# SD_Card_WCN_RF.net
KiCad netlist of a schematic drawn in Altium Designer
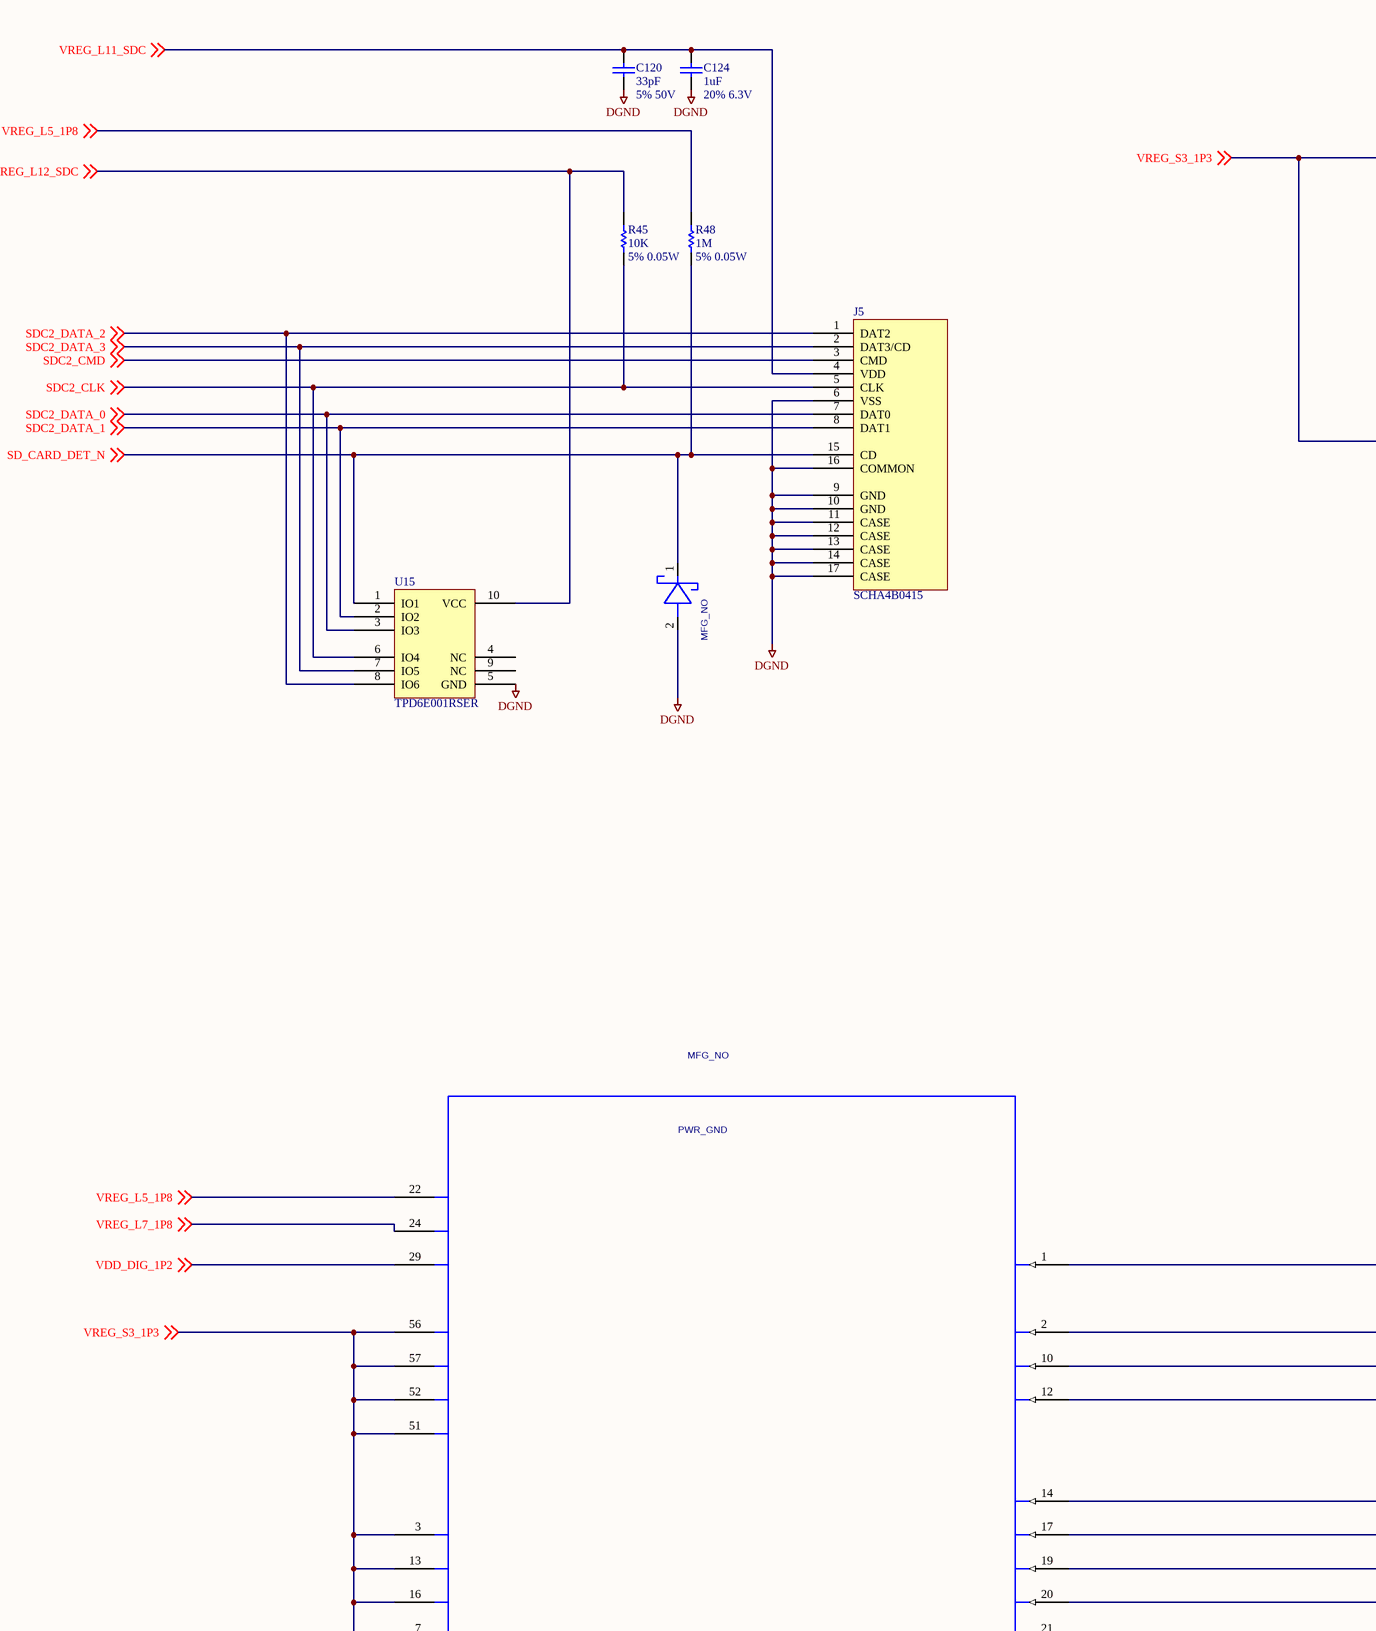
[diagram p0: SD Card_WCN_RF.SchDoc, top left]
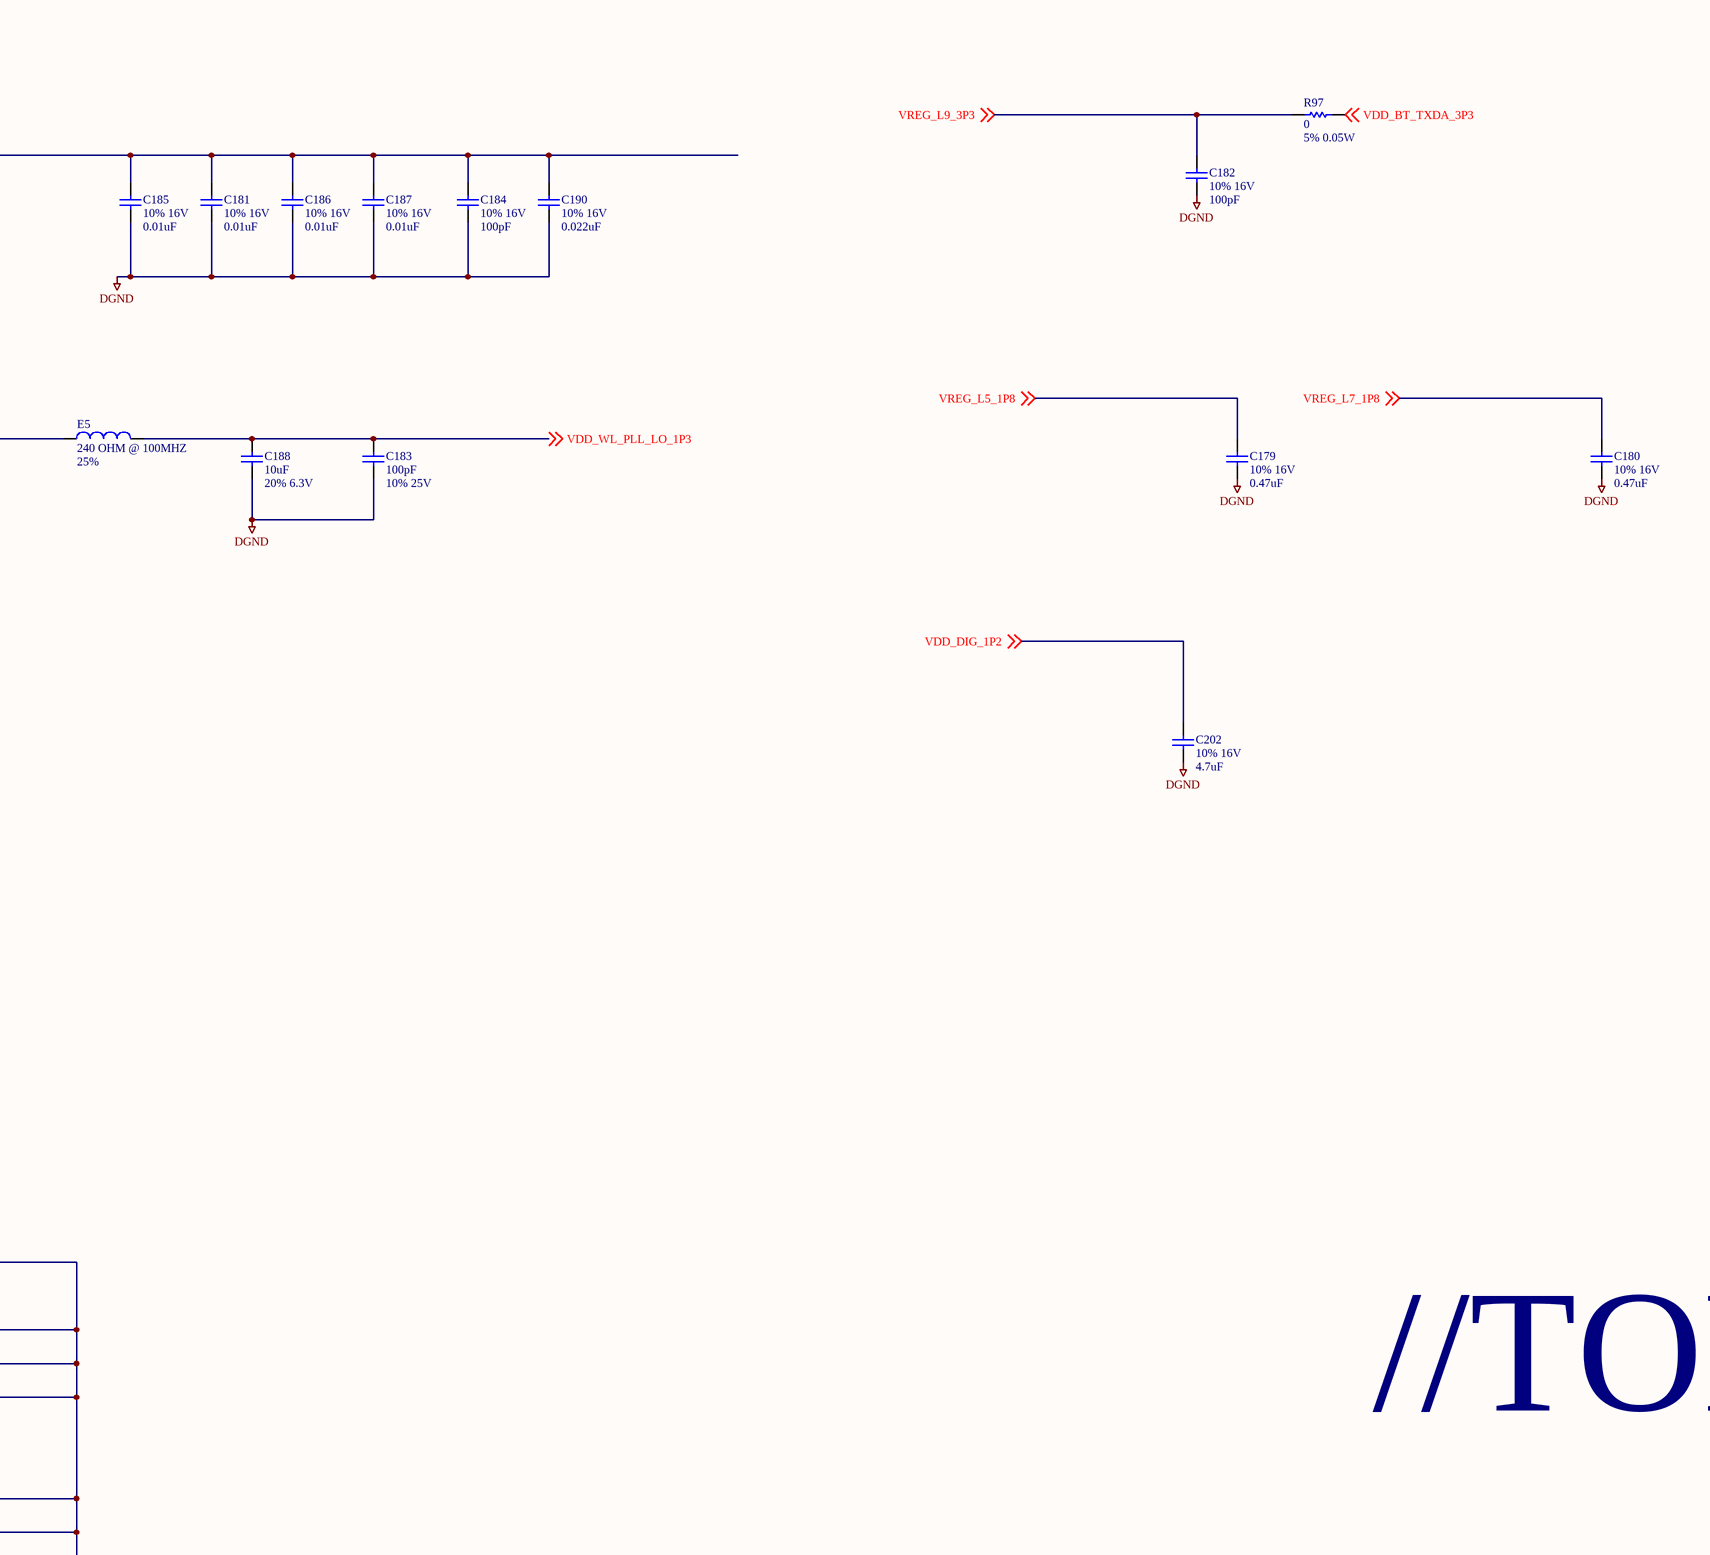
[diagram p1: SD Card_WCN_RF.SchDoc, top middle]
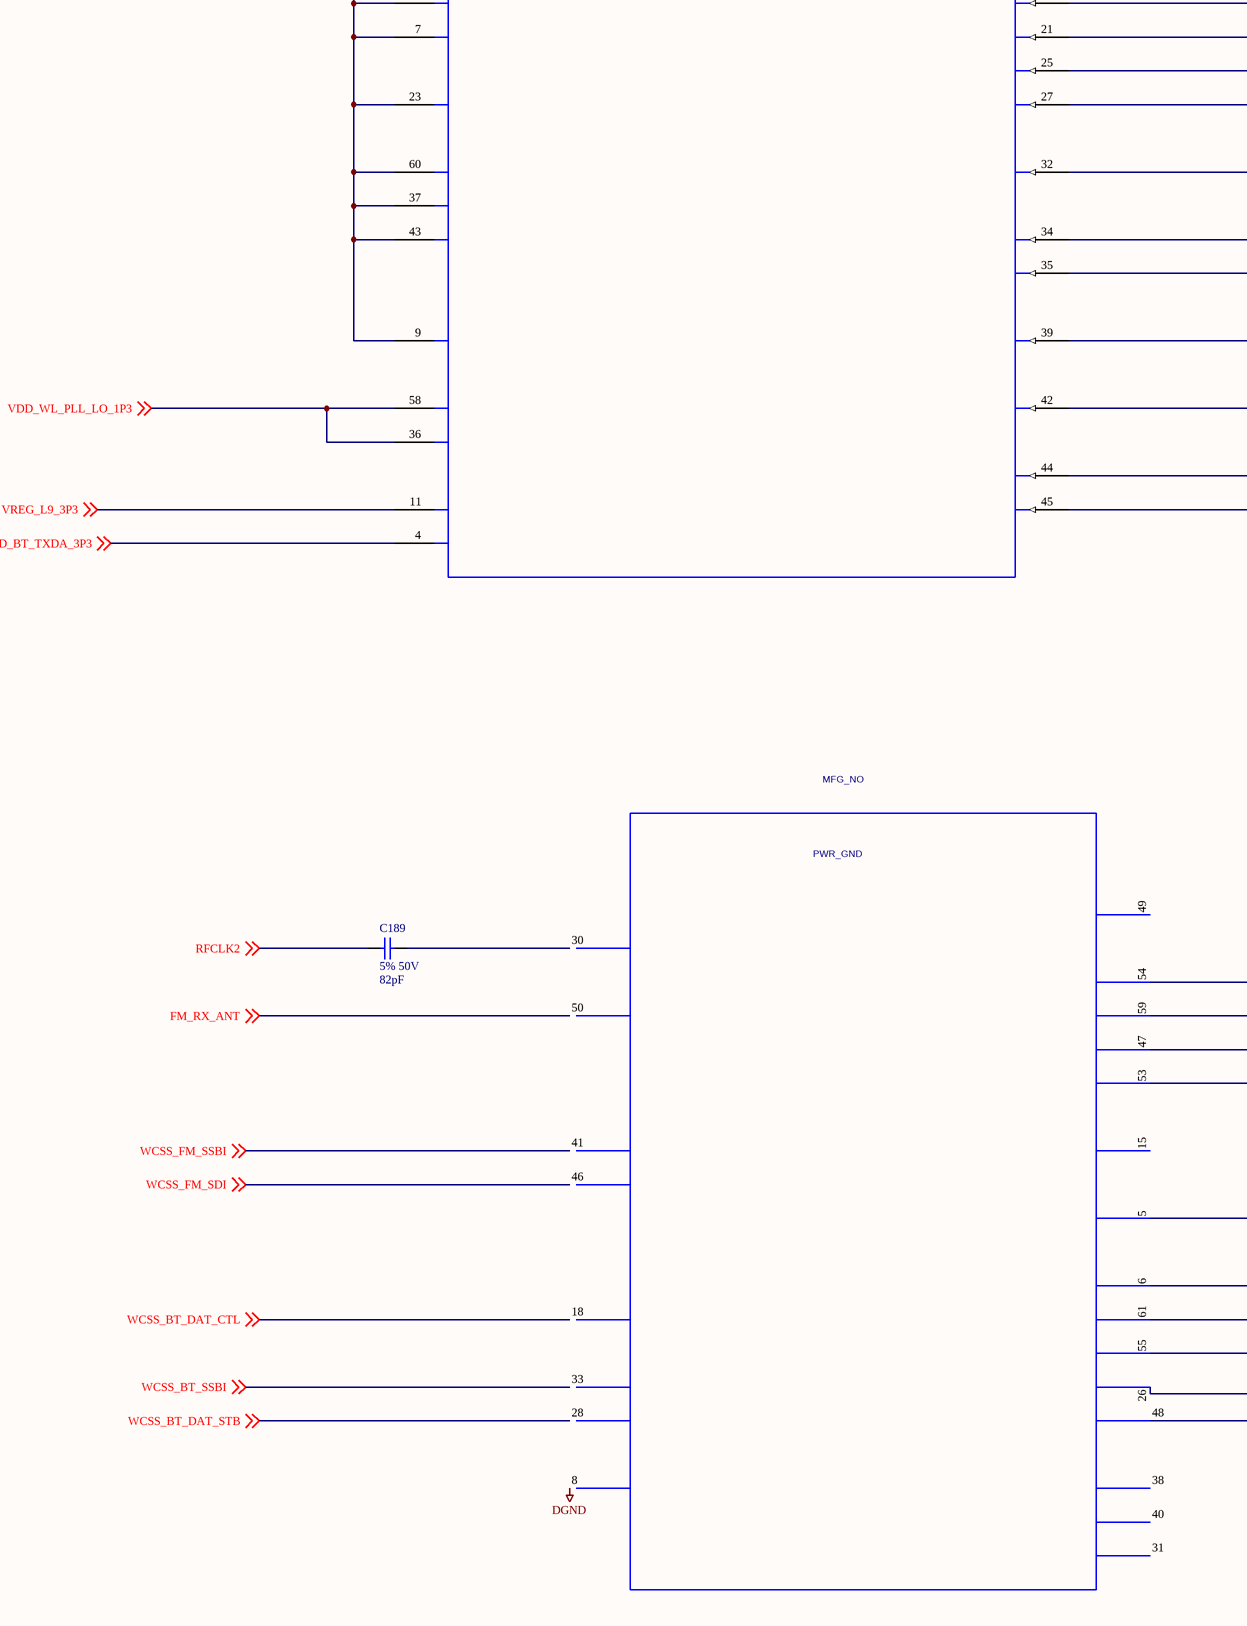
[diagram p2: SD Card_WCN_RF.SchDoc, bottom left]
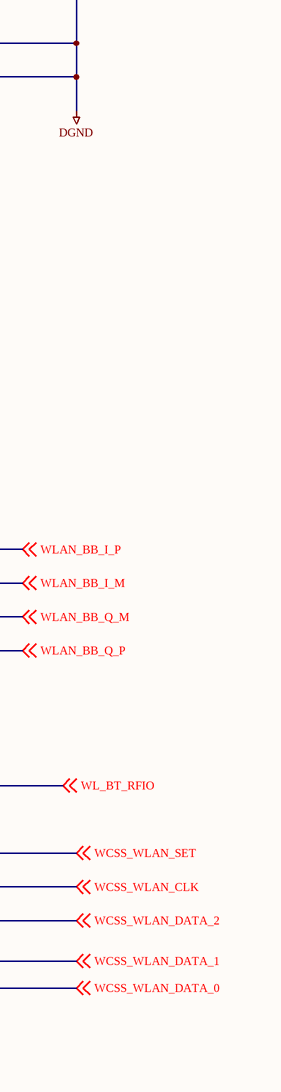
[diagram p3: SD Card_WCN_RF.SchDoc, bottom middle]

(export (version "E")
  (design (tool "Eeschema 10.0.6"))
  (components
    (comp (ref "C120")
      (value "33pF")
      (footprint "RAD-0.3")
      (description "Capacitor")
      (fields (field (name "ALTIUM_VALUE") "5% 50V") (field (name "PUBLISHER") "Altium Limited"))
      (libsource (lib "Miscellaneous Devices") (part "Cap"))
    )
    (comp (ref "C124")
      (value "1uF")
      (footprint "RAD-0.3")
      (description "Capacitor")
      (fields (field (name "ALTIUM_VALUE") "20% 6.3V") (field (name "PUBLISHER") "Altium Limited"))
      (libsource (lib "Miscellaneous Devices") (part "Cap"))
    )
    (comp (ref "C179")
      (value "10% 16V")
      (footprint "RAD-0.3")
      (description "Capacitor")
      (fields (field (name "ALTIUM_VALUE") "0.47uF") (field (name "PUBLISHER") "Altium Limited"))
      (libsource (lib "Miscellaneous Devices") (part "Cap"))
    )
    (comp (ref "C180")
      (value "10% 16V")
      (footprint "RAD-0.3")
      (description "Capacitor")
      (fields (field (name "ALTIUM_VALUE") "0.47uF") (field (name "PUBLISHER") "Altium Limited"))
      (libsource (lib "Miscellaneous Devices") (part "Cap"))
    )
    (comp (ref "C181")
      (value "10% 16V")
      (footprint "RAD-0.3")
      (description "Capacitor")
      (fields (field (name "ALTIUM_VALUE") "0.01uF") (field (name "PUBLISHER") "Altium Limited"))
      (libsource (lib "Miscellaneous Devices") (part "Cap"))
    )
    (comp (ref "C182")
      (value "10% 16V")
      (footprint "RAD-0.3")
      (description "Capacitor")
      (fields (field (name "ALTIUM_VALUE") "100pF") (field (name "PUBLISHER") "Altium Limited"))
      (libsource (lib "Miscellaneous Devices") (part "Cap"))
    )
    (comp (ref "C183")
      (value "100pF")
      (footprint "RAD-0.3")
      (description "Capacitor")
      (fields (field (name "ALTIUM_VALUE") "10% 25V") (field (name "PUBLISHER") "Altium Limited"))
      (libsource (lib "Miscellaneous Devices") (part "Cap"))
    )
    (comp (ref "C184")
      (value "10% 16V")
      (footprint "RAD-0.3")
      (description "Capacitor")
      (fields (field (name "ALTIUM_VALUE") "100pF") (field (name "PUBLISHER") "Altium Limited"))
      (libsource (lib "Miscellaneous Devices") (part "Cap"))
    )
    (comp (ref "C185")
      (value "10% 16V")
      (footprint "RAD-0.3")
      (description "Capacitor")
      (fields (field (name "ALTIUM_VALUE") "0.01uF") (field (name "PUBLISHER") "Altium Limited"))
      (libsource (lib "Miscellaneous Devices") (part "Cap"))
    )
    (comp (ref "C186")
      (value "10% 16V")
      (footprint "RAD-0.3")
      (description "Capacitor")
      (fields (field (name "ALTIUM_VALUE") "0.01uF") (field (name "PUBLISHER") "Altium Limited"))
      (libsource (lib "Miscellaneous Devices") (part "Cap"))
    )
    (comp (ref "C187")
      (value "10% 16V")
      (footprint "RAD-0.3")
      (description "Capacitor")
      (fields (field (name "ALTIUM_VALUE") "0.01uF") (field (name "PUBLISHER") "Altium Limited"))
      (libsource (lib "Miscellaneous Devices") (part "Cap"))
    )
    (comp (ref "C188")
      (value "10uF")
      (footprint "RAD-0.3")
      (description "Capacitor")
      (fields (field (name "ALTIUM_VALUE") "20% 6.3V") (field (name "PUBLISHER") "Altium Limited"))
      (libsource (lib "Miscellaneous Devices") (part "Cap"))
    )
    (comp (ref "C189")
      (value "5% 50V")
      (footprint "RAD-0.3")
      (description "Capacitor")
      (fields (field (name "ALTIUM_VALUE") "82pF") (field (name "PUBLISHER") "Altium Limited"))
      (libsource (lib "Miscellaneous Devices") (part "Cap"))
    )
    (comp (ref "C190")
      (value "10% 16V")
      (footprint "RAD-0.3")
      (description "Capacitor")
      (fields (field (name "ALTIUM_VALUE") "0.022uF") (field (name "PUBLISHER") "Altium Limited"))
      (libsource (lib "Miscellaneous Devices") (part "Cap"))
    )
    (comp (ref "C202")
      (value "10% 16V")
      (footprint "RAD-0.3")
      (description "Capacitor")
      (fields (field (name "ALTIUM_VALUE") "4.7uF") (field (name "PUBLISHER") "Altium Limited"))
      (libsource (lib "Miscellaneous Devices") (part "Cap"))
    )
    (comp (ref "CR24")
      (value "ESD7C5")
      (fields (field (name "PART_NUMBER") "MCN_NO") (field (name "PART_ID") "MFG_NO"))
      (libsource (lib "MSM8916_DRAM_PMIC_REF_Library") (part "SCHOTTKY"))
    )
    (comp (ref "E5")
      (value "240 OHM @ 100MHZ")
      (footprint "0402-A")
      (description "Inductor")
      (fields (field (name "ALTIUM_VALUE") "25%") (field (name "PUBLISHER") "Altium Limited"))
      (libsource (lib "Miscellaneous Devices") (part "Inductor"))
    )
    (comp (ref "J5")
      (value "SCHA4B0415")
      (libsource (lib "MSM8916_DRAM_PMIC_REF_Library") (part "SCHA4B0415"))
    )
    (comp (ref "R45")
      (value "10K")
      (footprint "AXIAL-0.3")
      (description "Resistor")
      (fields (field (name "ALTIUM_VALUE") "5% 0.05W") (field (name "PUBLISHER") "Altium Limited"))
      (libsource (lib "Miscellaneous Devices") (part "Res1"))
    )
    (comp (ref "R48")
      (value "1M")
      (footprint "AXIAL-0.3")
      (description "Resistor")
      (fields (field (name "ALTIUM_VALUE") "5% 0.05W") (field (name "PUBLISHER") "Altium Limited"))
      (libsource (lib "Miscellaneous Devices") (part "Res1"))
    )
    (comp (ref "R97")
      (value "0")
      (footprint "AXIAL-0.3")
      (description "Resistor")
      (fields (field (name "ALTIUM_VALUE") "5% 0.05W") (field (name "PUBLISHER") "Altium Limited"))
      (libsource (lib "Miscellaneous Devices") (part "Res1"))
    )
    (comp (ref "U9")
      (value "ASIC_WCN3620_80_WL006_1")
      (footprint "WCN-3620-0-61WLNSP-TR-05-0")
      (fields
        (field (name "PART_NUMBER") "MCN_NO")
        (field (name "SYMNAME") "PWR_GND")
        (field (name "PART_ID") "MFG_NO")
      )
      (libsource (lib "MSM8916_DRAM_PMIC_REF_Library") (part "ASIC_WCN3620_80_WL006_1"))
    )
    (comp (ref "U15")
      (value "TPD6E001RSER")
      (libsource (lib "MSM8916_DRAM_PMIC_REF_Library") (part "TPD6E001RSER"))
    )
  )
  (nets
    (net (code "1") (name "DGND") (class "Default")
      (node (ref "C120") (pin "1") (pinfunction "1_1") (pintype "passive"))
      (node (ref "C124") (pin "1") (pinfunction "1_1") (pintype "passive"))
      (node (ref "C179") (pin "1") (pinfunction "1_1") (pintype "passive"))
      (node (ref "C180") (pin "1") (pinfunction "1_1") (pintype "passive"))
      (node (ref "C181") (pin "1") (pinfunction "1_1") (pintype "passive"))
      (node (ref "C182") (pin "1") (pinfunction "1_1") (pintype "passive"))
      (node (ref "C183") (pin "1") (pinfunction "1_1") (pintype "passive"))
      (node (ref "C184") (pin "1") (pinfunction "1_1") (pintype "passive"))
      (node (ref "C185") (pin "1") (pinfunction "1_1") (pintype "passive"))
      (node (ref "C186") (pin "1") (pinfunction "1_1") (pintype "passive"))
      (node (ref "C187") (pin "1") (pinfunction "1_1") (pintype "passive"))
      (node (ref "C188") (pin "1") (pinfunction "1_1") (pintype "passive"))
      (node (ref "C190") (pin "1") (pinfunction "1_1") (pintype "passive"))
      (node (ref "C202") (pin "1") (pinfunction "1_1") (pintype "passive"))
      (node (ref "CR24") (pin "2") (pinfunction "POS_2") (pintype "bidirectional"))
      (node (ref "J5") (pin "10") (pinfunction "GND_10") (pintype "passive"))
      (node (ref "J5") (pin "11") (pinfunction "CASE_11") (pintype "passive"))
      (node (ref "J5") (pin "12") (pinfunction "CASE_12") (pintype "passive"))
      (node (ref "J5") (pin "13") (pinfunction "CASE_13") (pintype "passive"))
      (node (ref "J5") (pin "14") (pinfunction "CASE_14") (pintype "passive"))
      (node (ref "J5") (pin "16") (pinfunction "COMMON_16") (pintype "passive"))
      (node (ref "J5") (pin "17") (pinfunction "CASE_17") (pintype "passive"))
      (node (ref "J5") (pin "6") (pinfunction "VSS_6") (pintype "passive"))
      (node (ref "J5") (pin "9") (pinfunction "GND_9") (pintype "passive"))
      (node (ref "U15") (pin "5") (pinfunction "GND_5") (pintype "passive"))
      (node (ref "U9") (pin "1") (pinfunction "GND2_1") (pintype "input"))
      (node (ref "U9") (pin "10") (pinfunction "GND4_10") (pintype "input"))
      (node (ref "U9") (pin "12") (pinfunction "GND5_12") (pintype "input"))
      (node (ref "U9") (pin "14") (pinfunction "GND6_14") (pintype "input"))
      (node (ref "U9") (pin "17") (pinfunction "GND7_17") (pintype "input"))
      (node (ref "U9") (pin "19") (pinfunction "GND8_19") (pintype "input"))
      (node (ref "U9") (pin "2") (pinfunction "GND3_2") (pintype "input"))
      (node (ref "U9") (pin "20") (pinfunction "GND9_20") (pintype "input"))
      (node (ref "U9") (pin "21") (pinfunction "GND10_21") (pintype "input"))
      (node (ref "U9") (pin "25") (pinfunction "GND11_25") (pintype "input"))
      (node (ref "U9") (pin "27") (pinfunction "GND12_27") (pintype "input"))
      (node (ref "U9") (pin "32") (pinfunction "GND13_32") (pintype "input"))
      (node (ref "U9") (pin "34") (pinfunction "GND14_34") (pintype "input"))
      (node (ref "U9") (pin "35") (pinfunction "GND15_35") (pintype "input"))
      (node (ref "U9") (pin "39") (pinfunction "GND16_39") (pintype "input"))
      (node (ref "U9") (pin "42") (pinfunction "GND17_42") (pintype "input"))
      (node (ref "U9") (pin "44") (pinfunction "GND18_44") (pintype "input"))
      (node (ref "U9") (pin "45") (pinfunction "GND19_45") (pintype "input"))
      (node (ref "U9") (pin "8") (pinfunction "GND1_8") (pintype "input"))
    )
    (net (code "2") (name "FM_RX_ANT") (class "Default")
      (node (ref "U9") (pin "50") (pinfunction "FM_HS_RX_50") (pintype "bidirectional"))
    )
    (net (code "3") (name "Net-(U9A-TCXO_IN)") (class "Default")
      (node (ref "C189") (pin "1") (pinfunction "1_1") (pintype "passive"))
      (node (ref "U9") (pin "30") (pinfunction "TCXO_IN_30") (pintype "bidirectional"))
    )
    (net (code "4") (name "RFCLK2") (class "Default")
      (node (ref "C189") (pin "2") (pinfunction "2_2") (pintype "passive"))
    )
    (net (code "5") (name "SDC2_CLK") (class "Default")
      (node (ref "J5") (pin "5") (pinfunction "CLK_5") (pintype "passive"))
      (node (ref "R45") (pin "1") (pinfunction "1_1") (pintype "passive"))
      (node (ref "U15") (pin "6") (pinfunction "IO4_6") (pintype "passive"))
    )
    (net (code "6") (name "SDC2_CMD") (class "Default")
      (node (ref "J5") (pin "3") (pinfunction "CMD_3") (pintype "passive"))
    )
    (net (code "7") (name "SDC2_DATA_0") (class "Default")
      (node (ref "J5") (pin "7") (pinfunction "DAT0_7") (pintype "passive"))
      (node (ref "U15") (pin "3") (pinfunction "IO3_3") (pintype "passive"))
    )
    (net (code "8") (name "SDC2_DATA_1") (class "Default")
      (node (ref "J5") (pin "8") (pinfunction "DAT1_8") (pintype "passive"))
      (node (ref "U15") (pin "2") (pinfunction "IO2_2") (pintype "passive"))
    )
    (net (code "9") (name "SDC2_DATA_2") (class "Default")
      (node (ref "J5") (pin "1") (pinfunction "DAT2_1") (pintype "passive"))
      (node (ref "U15") (pin "8") (pinfunction "IO6_8") (pintype "passive"))
    )
    (net (code "10") (name "SDC2_DATA_3") (class "Default")
      (node (ref "J5") (pin "2") (pinfunction "DAT3/CD_2") (pintype "passive"))
      (node (ref "U15") (pin "7") (pinfunction "IO5_7") (pintype "passive"))
    )
    (net (code "11") (name "SD_CARD_DET_N") (class "Default")
      (node (ref "CR24") (pin "1") (pinfunction "NEG_1") (pintype "bidirectional"))
      (node (ref "J5") (pin "15") (pinfunction "CD_15") (pintype "passive"))
      (node (ref "R48") (pin "1") (pinfunction "1_1") (pintype "passive"))
      (node (ref "U15") (pin "1") (pinfunction "IO1_1") (pintype "passive"))
    )
    (net (code "12") (name "VDD_BT_TXDA_3P3") (class "Default")
      (node (ref "R97") (pin "2") (pinfunction "2_2") (pintype "passive"))
      (node (ref "U9") (pin "4") (pinfunction "VDD_BT_DA_3P0_4") (pintype "power_in"))
    )
    (net (code "13") (name "VDD_DIG_1P2") (class "Default")
      (node (ref "C202") (pin "2") (pinfunction "2_2") (pintype "passive"))
      (node (ref "U9") (pin "29") (pinfunction "VDD_DIG_1P2_29") (pintype "power_in"))
    )
    (net (code "14") (name "VDD_WL_PLL_LO_1P3") (class "Default")
      (node (ref "C183") (pin "2") (pinfunction "2_2") (pintype "passive"))
      (node (ref "C188") (pin "2") (pinfunction "2_2") (pintype "passive"))
      (node (ref "E5") (pin "2") (pinfunction "2_2") (pintype "passive"))
      (node (ref "U9") (pin "36") (pinfunction "VDD_WL_LO_1P3_36") (pintype "power_in"))
      (node (ref "U9") (pin "58") (pinfunction "VDD_WL_PLL_1P3_58") (pintype "power_in"))
    )
    (net (code "15") (name "VREG_L5_1P8") (class "Default")
      (node (ref "C179") (pin "2") (pinfunction "2_2") (pintype "passive"))
      (node (ref "R48") (pin "2") (pinfunction "2_2") (pintype "passive"))
      (node (ref "U9") (pin "22") (pinfunction "VDD_IO_1P8_22") (pintype "power_in"))
    )
    (net (code "16") (name "VREG_L7_1P8") (class "Default")
      (node (ref "C180") (pin "2") (pinfunction "2_2") (pintype "passive"))
      (node (ref "U9") (pin "24") (pinfunction "VDD_XO_1P8_24") (pintype "power_in"))
    )
    (net (code "17") (name "VREG_L9_3P3") (class "Default")
      (node (ref "C182") (pin "2") (pinfunction "2_2") (pintype "passive"))
      (node (ref "R97") (pin "1") (pinfunction "1_1") (pintype "passive"))
      (node (ref "U9") (pin "11") (pinfunction "VDD_WL_2GPA_3P0_11") (pintype "power_in"))
    )
    (net (code "18") (name "VREG_L11_SDC") (class "Default")
      (node (ref "C120") (pin "2") (pinfunction "2_2") (pintype "passive"))
      (node (ref "C124") (pin "2") (pinfunction "2_2") (pintype "passive"))
      (node (ref "J5") (pin "4") (pinfunction "VDD_4") (pintype "passive"))
    )
    (net (code "19") (name "VREG_L12_SDC") (class "Default")
      (node (ref "R45") (pin "2") (pinfunction "2_2") (pintype "passive"))
      (node (ref "U15") (pin "10") (pinfunction "VCC_10") (pintype "passive"))
    )
    (net (code "20") (name "VREG_S3_1P3") (class "Default")
      (node (ref "C181") (pin "2") (pinfunction "2_2") (pintype "passive"))
      (node (ref "C184") (pin "2") (pinfunction "2_2") (pintype "passive"))
      (node (ref "C185") (pin "2") (pinfunction "2_2") (pintype "passive"))
      (node (ref "C186") (pin "2") (pinfunction "2_2") (pintype "passive"))
      (node (ref "C187") (pin "2") (pinfunction "2_2") (pintype "passive"))
      (node (ref "C190") (pin "2") (pinfunction "2_2") (pintype "passive"))
      (node (ref "E5") (pin "1") (pinfunction "1_1") (pintype "passive"))
      (node (ref "U9") (pin "13") (pinfunction "VDD_BT_BB_1P3_13") (pintype "power_in"))
      (node (ref "U9") (pin "16") (pinfunction "VDD_BT_PLL_1P3_16") (pintype "power_in"))
      (node (ref "U9") (pin "23") (pinfunction "VDD_BT_FM_DIG_1P3_23") (pintype "power_in"))
      (node (ref "U9") (pin "3") (pinfunction "VDD_BT_RF_1P3_3") (pintype "power_in"))
      (node (ref "U9") (pin "37") (pinfunction "VDD_WL_2GPA_1P3_37") (pintype "power_in"))
      (node (ref "U9") (pin "43") (pinfunction "VDD_WL_UPC_1P3_43") (pintype "power_in"))
      (node (ref "U9") (pin "51") (pinfunction "VDD_FM_VCO_1P3_51") (pintype "power_in"))
      (node (ref "U9") (pin "52") (pinfunction "VDD_FM_PLL_1P3_52") (pintype "power_in"))
      (node (ref "U9") (pin "56") (pinfunction "VDD_FM_RXFE_1P3_56") (pintype "power_in"))
      (node (ref "U9") (pin "57") (pinfunction "VDD_FM_RXBB_1P3_57") (pintype "power_in"))
      (node (ref "U9") (pin "60") (pinfunction "VDD_WL_BB_1P3_60") (pintype "power_in"))
      (node (ref "U9") (pin "7") (pinfunction "VDD_BT_VCO_1P3_7") (pintype "power_in"))
      (node (ref "U9") (pin "9") (pinfunction "VDD_WL_2GLNA_1P3_9") (pintype "power_in"))
    )
    (net (code "21") (name "WCSS_BT_DAT_CTL") (class "Default")
      (node (ref "U9") (pin "18") (pinfunction "BT_CTL_18") (pintype "bidirectional"))
    )
    (net (code "22") (name "WCSS_BT_DAT_STB") (class "Default")
      (node (ref "U9") (pin "28") (pinfunction "BT_DATA_28") (pintype "bidirectional"))
    )
    (net (code "23") (name "WCSS_BT_SSBI") (class "Default")
      (node (ref "U9") (pin "33") (pinfunction "BT_SSBI_33") (pintype "bidirectional"))
    )
    (net (code "24") (name "WCSS_FM_SDI") (class "Default")
      (node (ref "U9") (pin "46") (pinfunction "FM_DATA_46") (pintype "bidirectional"))
    )
    (net (code "25") (name "WCSS_FM_SSBI") (class "Default")
      (node (ref "U9") (pin "41") (pinfunction "FM_SSBI_41") (pintype "bidirectional"))
    )
    (net (code "26") (name "WCSS_WLAN_CLK") (class "Default")
      (node (ref "U9") (pin "61") (pinfunction "WL_CMD_CLK_61") (pintype "bidirectional"))
    )
    (net (code "27") (name "WCSS_WLAN_DATA_0") (class "Default")
      (node (ref "U9") (pin "48") (pinfunction "WL_CMD_DATA0_48") (pintype "bidirectional"))
    )
    (net (code "28") (name "WCSS_WLAN_DATA_1") (class "Default")
      (node (ref "U9") (pin "26") (pinfunction "WL_CMD_DATA1_26") (pintype "bidirectional"))
    )
    (net (code "29") (name "WCSS_WLAN_DATA_2") (class "Default")
      (node (ref "U9") (pin "55") (pinfunction "WL_CMD_DATA2_55") (pintype "bidirectional"))
    )
    (net (code "30") (name "WCSS_WLAN_SET") (class "Default")
      (node (ref "U9") (pin "6") (pinfunction "WL_CMD_SET_6") (pintype "bidirectional"))
    )
    (net (code "31") (name "WLAN_BB_I_M") (class "Default")
      (node (ref "U9") (pin "59") (pinfunction "WL_BB_IN_59") (pintype "bidirectional"))
    )
    (net (code "32") (name "WLAN_BB_I_P") (class "Default")
      (node (ref "U9") (pin "54") (pinfunction "WL_BB_IP_54") (pintype "bidirectional"))
    )
    (net (code "33") (name "WLAN_BB_Q_M") (class "Default")
      (node (ref "U9") (pin "47") (pinfunction "WL_BB_QN_47") (pintype "bidirectional"))
    )
    (net (code "34") (name "WLAN_BB_Q_P") (class "Default")
      (node (ref "U9") (pin "53") (pinfunction "WL_BB_QP_53") (pintype "bidirectional"))
    )
    (net (code "35") (name "WL_BT_RFIO") (class "Default")
      (node (ref "U9") (pin "5") (pinfunction "WL_BT_RFIO_5") (pintype "bidirectional"))
    )
    (net (code "36") (name "unconnected-(U9A-NC1-Pad15)") (class "Default")
      (node (ref "U9") (pin "15") (pinfunction "NC1_15") (pintype "bidirectional"))
    )
    (net (code "37") (name "unconnected-(U9A-NC2-Pad31)") (class "Default")
      (node (ref "U9") (pin "31") (pinfunction "NC2_31") (pintype "bidirectional"))
    )
    (net (code "38") (name "unconnected-(U9A-NC3-Pad40)") (class "Default")
      (node (ref "U9") (pin "40") (pinfunction "NC3_40") (pintype "bidirectional"))
    )
    (net (code "39") (name "unconnected-(U9A-NC4-Pad38)") (class "Default")
      (node (ref "U9") (pin "38") (pinfunction "NC4_38") (pintype "bidirectional"))
    )
    (net (code "40") (name "unconnected-(U9A-WL_PDET_IN-Pad49)") (class "Default")
      (node (ref "U9") (pin "49") (pinfunction "WL_PDET_IN_49") (pintype "bidirectional"))
    )
    (net (code "41") (name "unconnected-(U15-NC-Pad4)") (class "Default")
      (node (ref "U15") (pin "4") (pinfunction "NC_4") (pintype "passive"))
    )
    (net (code "42") (name "unconnected-(U15-NC-Pad9)") (class "Default")
      (node (ref "U15") (pin "9") (pinfunction "NC_9") (pintype "passive"))
    )
  )
)
